# 3DPOV.net
KiCad netlist of a schematic drawn in EAGLE
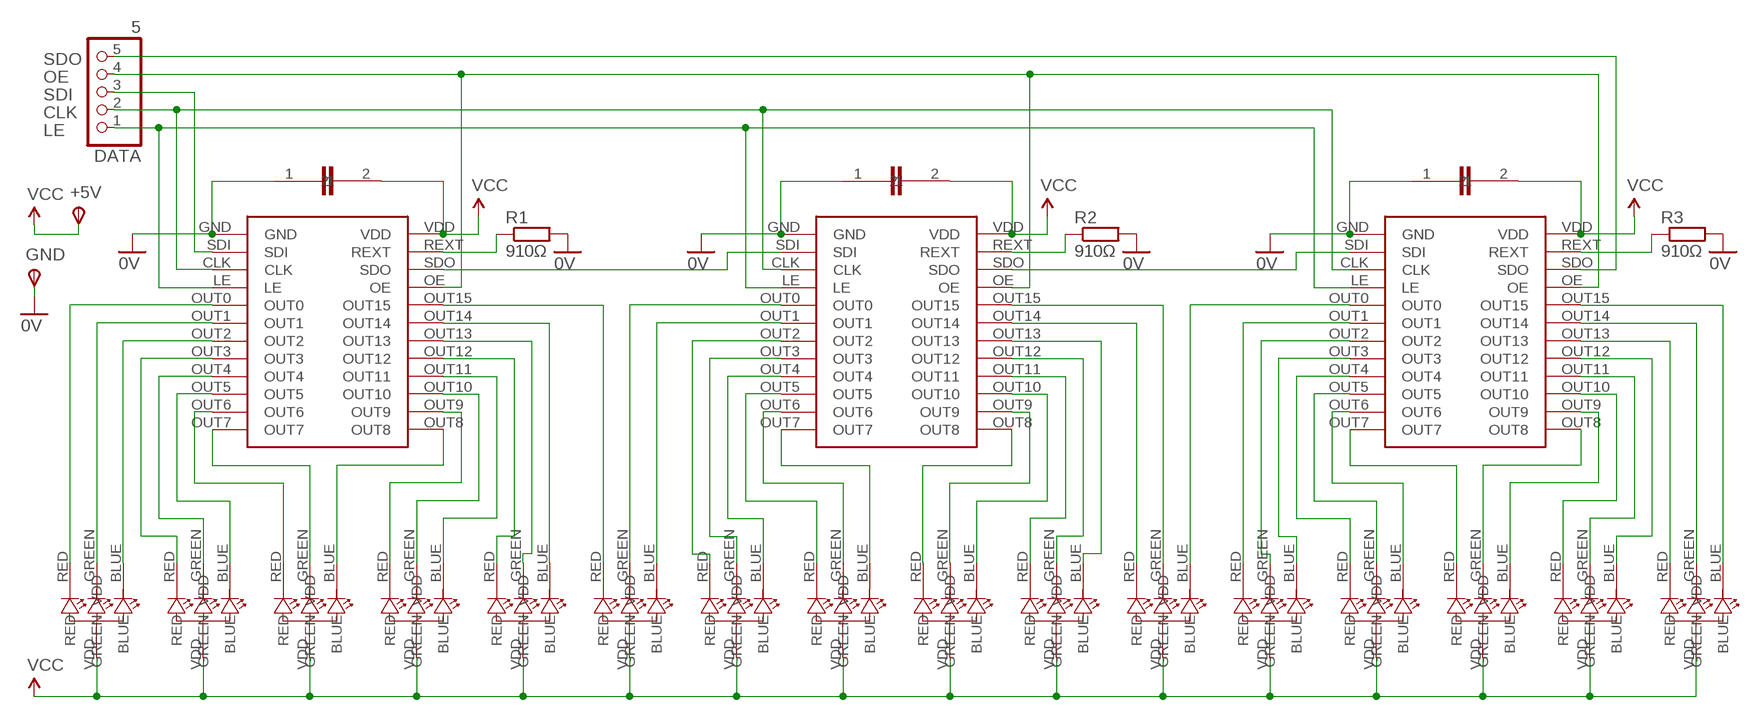
[diagram p0: schematic, sheet 1]

(export (version "E")
  (design (tool "Eeschema 10.0.6"))
  (components
    (comp (ref "+5V")
      (value "TPSPAD1-20")
      (footprint "eagle-import:P1-20")
      (libsource (lib "eagle-import") (part "TPSPAD1-20"))
    )
    (comp (ref "CAP1")
      (value "1µF")
      (footprint "eagle-import:CAP")
      (libsource (lib "eagle-import") (part "CAP"))
    )
    (comp (ref "CAP2")
      (value "1µF")
      (footprint "eagle-import:CAP")
      (libsource (lib "eagle-import") (part "CAP"))
    )
    (comp (ref "CAP3")
      (value "1µF")
      (footprint "eagle-import:CAP")
      (libsource (lib "eagle-import") (part "CAP"))
    )
    (comp (ref "DATA")
      (value "5")
      (footprint "eagle-import:1X05")
      (libsource (lib "eagle-import") (part "PINHD-1X5"))
    )
    (comp (ref "GND")
      (value "TPSPAD1-20")
      (footprint "eagle-import:P1-20")
      (libsource (lib "eagle-import") (part "TPSPAD1-20"))
    )
    (comp (ref "IC1")
      (value "TLC5927")
      (footprint "eagle-import:DBQ")
      (libsource (lib "eagle-import") (part "TLC5927"))
    )
    (comp (ref "IC2")
      (value "TLC5927")
      (footprint "eagle-import:DBQ")
      (libsource (lib "eagle-import") (part "TLC5927"))
    )
    (comp (ref "IC3")
      (value "TLC5927")
      (footprint "eagle-import:DBQ")
      (libsource (lib "eagle-import") (part "TLC5927"))
    )
    (comp (ref "R1")
      (value "910Ω")
      (footprint "eagle-import:0207_7")
      (libsource (lib "eagle-import") (part "R-EU_0207/7"))
    )
    (comp (ref "R2")
      (value "910Ω")
      (footprint "eagle-import:0207_7")
      (libsource (lib "eagle-import") (part "R-EU_0207/7"))
    )
    (comp (ref "R3")
      (value "910Ω")
      (footprint "eagle-import:0207_7")
      (libsource (lib "eagle-import") (part "R-EU_0207/7"))
    )
    (comp (ref "U$1")
      (value "SMDLED")
      (footprint "eagle-import:SMDLED")
      (libsource (lib "eagle-import") (part "SMDLED"))
    )
    (comp (ref "U$2")
      (value "SMDLED")
      (footprint "eagle-import:SMDLED")
      (libsource (lib "eagle-import") (part "SMDLED"))
    )
    (comp (ref "U$4")
      (value "SMDLED")
      (footprint "eagle-import:SMDLED")
      (libsource (lib "eagle-import") (part "SMDLED"))
    )
    (comp (ref "U$5")
      (value "SMDLED")
      (footprint "eagle-import:SMDLED")
      (libsource (lib "eagle-import") (part "SMDLED"))
    )
    (comp (ref "U$6")
      (value "SMDLED")
      (footprint "eagle-import:SMDLED")
      (libsource (lib "eagle-import") (part "SMDLED"))
    )
    (comp (ref "U$7")
      (value "SMDLED")
      (footprint "eagle-import:SMDLED")
      (libsource (lib "eagle-import") (part "SMDLED"))
    )
    (comp (ref "U$10")
      (value "SMDLED")
      (footprint "eagle-import:SMDLED")
      (libsource (lib "eagle-import") (part "SMDLED"))
    )
    (comp (ref "U$11")
      (value "SMDLED")
      (footprint "eagle-import:SMDLED")
      (libsource (lib "eagle-import") (part "SMDLED"))
    )
    (comp (ref "U$12")
      (value "SMDLED")
      (footprint "eagle-import:SMDLED")
      (libsource (lib "eagle-import") (part "SMDLED"))
    )
    (comp (ref "U$13")
      (value "SMDLED")
      (footprint "eagle-import:SMDLED")
      (libsource (lib "eagle-import") (part "SMDLED"))
    )
    (comp (ref "U$14")
      (value "SMDLED")
      (footprint "eagle-import:SMDLED")
      (libsource (lib "eagle-import") (part "SMDLED"))
    )
    (comp (ref "U$15")
      (value "SMDLED")
      (footprint "eagle-import:SMDLED")
      (libsource (lib "eagle-import") (part "SMDLED"))
    )
    (comp (ref "U$16")
      (value "SMDLED")
      (footprint "eagle-import:SMDLED")
      (libsource (lib "eagle-import") (part "SMDLED"))
    )
    (comp (ref "U$17")
      (value "SMDLED")
      (footprint "eagle-import:SMDLED")
      (libsource (lib "eagle-import") (part "SMDLED"))
    )
    (comp (ref "U$18")
      (value "SMDLED")
      (footprint "eagle-import:SMDLED")
      (libsource (lib "eagle-import") (part "SMDLED"))
    )
    (comp (ref "U$19")
      (value "SMDLED")
      (footprint "eagle-import:SMDLED")
      (libsource (lib "eagle-import") (part "SMDLED"))
    )
  )
  (nets
    (net (code "1") (name "/CLK") (class "Default")
      (node (ref "DATA") (pin "2") (pinfunction "2_2") (pintype "passive"))
      (node (ref "IC1") (pin "CLK") (pinfunction "CLK_CLK") (pintype "bidirectional"))
      (node (ref "IC2") (pin "CLK") (pinfunction "CLK_CLK") (pintype "bidirectional"))
      (node (ref "IC3") (pin "CLK") (pinfunction "CLK_CLK") (pintype "bidirectional"))
    )
    (net (code "2") (name "/LE") (class "Default")
      (node (ref "DATA") (pin "1") (pinfunction "1_1") (pintype "passive"))
      (node (ref "IC1") (pin "LE") (pinfunction "LE_LE") (pintype "bidirectional"))
      (node (ref "IC2") (pin "LE") (pinfunction "LE_LE") (pintype "bidirectional"))
      (node (ref "IC3") (pin "LE") (pinfunction "LE_LE") (pintype "bidirectional"))
    )
    (net (code "3") (name "/OE") (class "Default")
      (node (ref "DATA") (pin "4") (pinfunction "4_4") (pintype "passive"))
      (node (ref "IC1") (pin "OE") (pinfunction "OE_OE") (pintype "bidirectional"))
      (node (ref "IC2") (pin "OE") (pinfunction "OE_OE") (pintype "bidirectional"))
      (node (ref "IC3") (pin "OE") (pinfunction "OE_OE") (pintype "bidirectional"))
    )
    (net (code "4") (name "/SDI") (class "Default")
      (node (ref "DATA") (pin "3") (pinfunction "3_3") (pintype "passive"))
      (node (ref "IC1") (pin "SDI") (pinfunction "SDI_SDI") (pintype "bidirectional"))
    )
    (net (code "5") (name "/SDO") (class "Default")
      (node (ref "DATA") (pin "5") (pinfunction "5_5") (pintype "passive"))
      (node (ref "IC3") (pin "SDO") (pinfunction "SDO_SDO") (pintype "bidirectional"))
    )
    (net (code "6") (name "0V") (class "Default")
      (node (ref "CAP1") (pin "1") (pinfunction "1_1") (pintype "bidirectional"))
      (node (ref "CAP2") (pin "1") (pinfunction "1_1") (pintype "bidirectional"))
      (node (ref "CAP3") (pin "1") (pinfunction "1_1") (pintype "bidirectional"))
      (node (ref "GND") (pin "TP") (pinfunction "PP_TP") (pintype "input"))
      (node (ref "IC1") (pin "GND") (pinfunction "GND_GND") (pintype "bidirectional"))
      (node (ref "IC2") (pin "GND") (pinfunction "GND_GND") (pintype "bidirectional"))
      (node (ref "IC3") (pin "GND") (pinfunction "GND_GND") (pintype "bidirectional"))
      (node (ref "R1") (pin "2") (pinfunction "2_2") (pintype "passive"))
      (node (ref "R2") (pin "2") (pinfunction "2_2") (pintype "passive"))
      (node (ref "R3") (pin "2") (pinfunction "2_2") (pintype "passive"))
    )
    (net (code "7") (name "Net-(IC1-PadOUT0)") (class "Default")
      (node (ref "IC1") (pin "OUT0") (pinfunction "OUT0_OUT0") (pintype "bidirectional"))
      (node (ref "U$4") (pin "RED") (pinfunction "RED_RED") (pintype "bidirectional"))
    )
    (net (code "8") (name "Net-(IC1-PadOUT1)") (class "Default")
      (node (ref "IC1") (pin "OUT1") (pinfunction "OUT1_OUT1") (pintype "bidirectional"))
      (node (ref "U$4") (pin "GREEN") (pinfunction "GREEN_GREEN") (pintype "bidirectional"))
    )
    (net (code "9") (name "Net-(IC1-PadOUT2)") (class "Default")
      (node (ref "IC1") (pin "OUT2") (pinfunction "OUT2_OUT2") (pintype "bidirectional"))
      (node (ref "U$4") (pin "BLUE") (pinfunction "BLUE_BLUE") (pintype "bidirectional"))
    )
    (net (code "10") (name "Net-(IC1-PadOUT3)") (class "Default")
      (node (ref "IC1") (pin "OUT3") (pinfunction "OUT3_OUT3") (pintype "bidirectional"))
      (node (ref "U$5") (pin "RED") (pinfunction "RED_RED") (pintype "bidirectional"))
    )
    (net (code "11") (name "Net-(IC1-PadOUT4)") (class "Default")
      (node (ref "IC1") (pin "OUT4") (pinfunction "OUT4_OUT4") (pintype "bidirectional"))
      (node (ref "U$5") (pin "GREEN") (pinfunction "GREEN_GREEN") (pintype "bidirectional"))
    )
    (net (code "12") (name "Net-(IC1-PadOUT5)") (class "Default")
      (node (ref "IC1") (pin "OUT5") (pinfunction "OUT5_OUT5") (pintype "bidirectional"))
      (node (ref "U$5") (pin "BLUE") (pinfunction "BLUE_BLUE") (pintype "bidirectional"))
    )
    (net (code "13") (name "Net-(IC1-PadOUT6)") (class "Default")
      (node (ref "IC1") (pin "OUT6") (pinfunction "OUT6_OUT6") (pintype "bidirectional"))
      (node (ref "U$6") (pin "RED") (pinfunction "RED_RED") (pintype "bidirectional"))
    )
    (net (code "14") (name "Net-(IC1-PadOUT7)") (class "Default")
      (node (ref "IC1") (pin "OUT7") (pinfunction "OUT7_OUT7") (pintype "bidirectional"))
      (node (ref "U$6") (pin "GREEN") (pinfunction "GREEN_GREEN") (pintype "bidirectional"))
    )
    (net (code "15") (name "Net-(IC1-PadOUT8)") (class "Default")
      (node (ref "IC1") (pin "OUT8") (pinfunction "OUT8_OUT8") (pintype "bidirectional"))
      (node (ref "U$6") (pin "BLUE") (pinfunction "BLUE_BLUE") (pintype "bidirectional"))
    )
    (net (code "16") (name "Net-(IC1-PadOUT9)") (class "Default")
      (node (ref "IC1") (pin "OUT9") (pinfunction "OUT9_OUT9") (pintype "bidirectional"))
      (node (ref "U$7") (pin "RED") (pinfunction "RED_RED") (pintype "bidirectional"))
    )
    (net (code "17") (name "Net-(IC1-PadOUT10)") (class "Default")
      (node (ref "IC1") (pin "OUT10") (pinfunction "OUT10_OUT10") (pintype "bidirectional"))
      (node (ref "U$7") (pin "GREEN") (pinfunction "GREEN_GREEN") (pintype "bidirectional"))
    )
    (net (code "18") (name "Net-(IC1-PadOUT11)") (class "Default")
      (node (ref "IC1") (pin "OUT11") (pinfunction "OUT11_OUT11") (pintype "bidirectional"))
      (node (ref "U$7") (pin "BLUE") (pinfunction "BLUE_BLUE") (pintype "bidirectional"))
    )
    (net (code "19") (name "Net-(IC1-PadOUT12)") (class "Default")
      (node (ref "IC1") (pin "OUT12") (pinfunction "OUT12_OUT12") (pintype "bidirectional"))
      (node (ref "U$2") (pin "RED") (pinfunction "RED_RED") (pintype "bidirectional"))
    )
    (net (code "20") (name "Net-(IC1-PadOUT13)") (class "Default")
      (node (ref "IC1") (pin "OUT13") (pinfunction "OUT13_OUT13") (pintype "bidirectional"))
      (node (ref "U$2") (pin "GREEN") (pinfunction "GREEN_GREEN") (pintype "bidirectional"))
    )
    (net (code "21") (name "Net-(IC1-PadOUT14)") (class "Default")
      (node (ref "IC1") (pin "OUT14") (pinfunction "OUT14_OUT14") (pintype "bidirectional"))
      (node (ref "U$2") (pin "BLUE") (pinfunction "BLUE_BLUE") (pintype "bidirectional"))
    )
    (net (code "22") (name "Net-(IC1-PadOUT15)") (class "Default")
      (node (ref "IC1") (pin "OUT15") (pinfunction "OUT15_OUT15") (pintype "bidirectional"))
      (node (ref "U$1") (pin "RED") (pinfunction "RED_RED") (pintype "bidirectional"))
    )
    (net (code "23") (name "Net-(IC1-PadREXT)") (class "Default")
      (node (ref "IC1") (pin "REXT") (pinfunction "REXT_REXT") (pintype "bidirectional"))
      (node (ref "R1") (pin "1") (pinfunction "1_1") (pintype "passive"))
    )
    (net (code "24") (name "Net-(IC1-PadSDO)") (class "Default")
      (node (ref "IC1") (pin "SDO") (pinfunction "SDO_SDO") (pintype "bidirectional"))
      (node (ref "IC2") (pin "SDI") (pinfunction "SDI_SDI") (pintype "bidirectional"))
    )
    (net (code "25") (name "Net-(IC2-PadOUT0)") (class "Default")
      (node (ref "IC2") (pin "OUT0") (pinfunction "OUT0_OUT0") (pintype "bidirectional"))
      (node (ref "U$1") (pin "GREEN") (pinfunction "GREEN_GREEN") (pintype "bidirectional"))
    )
    (net (code "26") (name "Net-(IC2-PadOUT1)") (class "Default")
      (node (ref "IC2") (pin "OUT1") (pinfunction "OUT1_OUT1") (pintype "bidirectional"))
      (node (ref "U$1") (pin "BLUE") (pinfunction "BLUE_BLUE") (pintype "bidirectional"))
    )
    (net (code "27") (name "Net-(IC2-PadOUT2)") (class "Default")
      (node (ref "IC2") (pin "OUT2") (pinfunction "OUT2_OUT2") (pintype "bidirectional"))
      (node (ref "U$10") (pin "RED") (pinfunction "RED_RED") (pintype "bidirectional"))
    )
    (net (code "28") (name "Net-(IC2-PadOUT3)") (class "Default")
      (node (ref "IC2") (pin "OUT3") (pinfunction "OUT3_OUT3") (pintype "bidirectional"))
      (node (ref "U$10") (pin "GREEN") (pinfunction "GREEN_GREEN") (pintype "bidirectional"))
    )
    (net (code "29") (name "Net-(IC2-PadOUT4)") (class "Default")
      (node (ref "IC2") (pin "OUT4") (pinfunction "OUT4_OUT4") (pintype "bidirectional"))
      (node (ref "U$10") (pin "BLUE") (pinfunction "BLUE_BLUE") (pintype "bidirectional"))
    )
    (net (code "30") (name "Net-(IC2-PadOUT5)") (class "Default")
      (node (ref "IC2") (pin "OUT5") (pinfunction "OUT5_OUT5") (pintype "bidirectional"))
      (node (ref "U$11") (pin "RED") (pinfunction "RED_RED") (pintype "bidirectional"))
    )
    (net (code "31") (name "Net-(IC2-PadOUT6)") (class "Default")
      (node (ref "IC2") (pin "OUT6") (pinfunction "OUT6_OUT6") (pintype "bidirectional"))
      (node (ref "U$11") (pin "GREEN") (pinfunction "GREEN_GREEN") (pintype "bidirectional"))
    )
    (net (code "32") (name "Net-(IC2-PadOUT7)") (class "Default")
      (node (ref "IC2") (pin "OUT7") (pinfunction "OUT7_OUT7") (pintype "bidirectional"))
      (node (ref "U$11") (pin "BLUE") (pinfunction "BLUE_BLUE") (pintype "bidirectional"))
    )
    (net (code "33") (name "Net-(IC2-PadOUT8)") (class "Default")
      (node (ref "IC2") (pin "OUT8") (pinfunction "OUT8_OUT8") (pintype "bidirectional"))
      (node (ref "U$12") (pin "RED") (pinfunction "RED_RED") (pintype "bidirectional"))
    )
    (net (code "34") (name "Net-(IC2-PadOUT9)") (class "Default")
      (node (ref "IC2") (pin "OUT9") (pinfunction "OUT9_OUT9") (pintype "bidirectional"))
      (node (ref "U$12") (pin "GREEN") (pinfunction "GREEN_GREEN") (pintype "bidirectional"))
    )
    (net (code "35") (name "Net-(IC2-PadOUT10)") (class "Default")
      (node (ref "IC2") (pin "OUT10") (pinfunction "OUT10_OUT10") (pintype "bidirectional"))
      (node (ref "U$12") (pin "BLUE") (pinfunction "BLUE_BLUE") (pintype "bidirectional"))
    )
    (net (code "36") (name "Net-(IC2-PadOUT11)") (class "Default")
      (node (ref "IC2") (pin "OUT11") (pinfunction "OUT11_OUT11") (pintype "bidirectional"))
      (node (ref "U$13") (pin "RED") (pinfunction "RED_RED") (pintype "bidirectional"))
    )
    (net (code "37") (name "Net-(IC2-PadOUT12)") (class "Default")
      (node (ref "IC2") (pin "OUT12") (pinfunction "OUT12_OUT12") (pintype "bidirectional"))
      (node (ref "U$13") (pin "GREEN") (pinfunction "GREEN_GREEN") (pintype "bidirectional"))
    )
    (net (code "38") (name "Net-(IC2-PadOUT13)") (class "Default")
      (node (ref "IC2") (pin "OUT13") (pinfunction "OUT13_OUT13") (pintype "bidirectional"))
      (node (ref "U$13") (pin "BLUE") (pinfunction "BLUE_BLUE") (pintype "bidirectional"))
    )
    (net (code "39") (name "Net-(IC2-PadOUT14)") (class "Default")
      (node (ref "IC2") (pin "OUT14") (pinfunction "OUT14_OUT14") (pintype "bidirectional"))
      (node (ref "U$14") (pin "RED") (pinfunction "RED_RED") (pintype "bidirectional"))
    )
    (net (code "40") (name "Net-(IC2-PadOUT15)") (class "Default")
      (node (ref "IC2") (pin "OUT15") (pinfunction "OUT15_OUT15") (pintype "bidirectional"))
      (node (ref "U$14") (pin "GREEN") (pinfunction "GREEN_GREEN") (pintype "bidirectional"))
    )
    (net (code "41") (name "Net-(IC2-PadREXT)") (class "Default")
      (node (ref "IC2") (pin "REXT") (pinfunction "REXT_REXT") (pintype "bidirectional"))
      (node (ref "R2") (pin "1") (pinfunction "1_1") (pintype "passive"))
    )
    (net (code "42") (name "Net-(IC2-PadSDO)") (class "Default")
      (node (ref "IC2") (pin "SDO") (pinfunction "SDO_SDO") (pintype "bidirectional"))
      (node (ref "IC3") (pin "SDI") (pinfunction "SDI_SDI") (pintype "bidirectional"))
    )
    (net (code "43") (name "Net-(IC3-PadOUT0)") (class "Default")
      (node (ref "IC3") (pin "OUT0") (pinfunction "OUT0_OUT0") (pintype "bidirectional"))
      (node (ref "U$14") (pin "BLUE") (pinfunction "BLUE_BLUE") (pintype "bidirectional"))
    )
    (net (code "44") (name "Net-(IC3-PadOUT1)") (class "Default")
      (node (ref "IC3") (pin "OUT1") (pinfunction "OUT1_OUT1") (pintype "bidirectional"))
      (node (ref "U$15") (pin "RED") (pinfunction "RED_RED") (pintype "bidirectional"))
    )
    (net (code "45") (name "Net-(IC3-PadOUT2)") (class "Default")
      (node (ref "IC3") (pin "OUT2") (pinfunction "OUT2_OUT2") (pintype "bidirectional"))
      (node (ref "U$15") (pin "GREEN") (pinfunction "GREEN_GREEN") (pintype "bidirectional"))
    )
    (net (code "46") (name "Net-(IC3-PadOUT3)") (class "Default")
      (node (ref "IC3") (pin "OUT3") (pinfunction "OUT3_OUT3") (pintype "bidirectional"))
      (node (ref "U$15") (pin "BLUE") (pinfunction "BLUE_BLUE") (pintype "bidirectional"))
    )
    (net (code "47") (name "Net-(IC3-PadOUT4)") (class "Default")
      (node (ref "IC3") (pin "OUT4") (pinfunction "OUT4_OUT4") (pintype "bidirectional"))
      (node (ref "U$16") (pin "RED") (pinfunction "RED_RED") (pintype "bidirectional"))
    )
    (net (code "48") (name "Net-(IC3-PadOUT5)") (class "Default")
      (node (ref "IC3") (pin "OUT5") (pinfunction "OUT5_OUT5") (pintype "bidirectional"))
      (node (ref "U$16") (pin "GREEN") (pinfunction "GREEN_GREEN") (pintype "bidirectional"))
    )
    (net (code "49") (name "Net-(IC3-PadOUT6)") (class "Default")
      (node (ref "IC3") (pin "OUT6") (pinfunction "OUT6_OUT6") (pintype "bidirectional"))
      (node (ref "U$16") (pin "BLUE") (pinfunction "BLUE_BLUE") (pintype "bidirectional"))
    )
    (net (code "50") (name "Net-(IC3-PadOUT7)") (class "Default")
      (node (ref "IC3") (pin "OUT7") (pinfunction "OUT7_OUT7") (pintype "bidirectional"))
      (node (ref "U$17") (pin "RED") (pinfunction "RED_RED") (pintype "bidirectional"))
    )
    (net (code "51") (name "Net-(IC3-PadOUT8)") (class "Default")
      (node (ref "IC3") (pin "OUT8") (pinfunction "OUT8_OUT8") (pintype "bidirectional"))
      (node (ref "U$17") (pin "GREEN") (pinfunction "GREEN_GREEN") (pintype "bidirectional"))
    )
    (net (code "52") (name "Net-(IC3-PadOUT9)") (class "Default")
      (node (ref "IC3") (pin "OUT9") (pinfunction "OUT9_OUT9") (pintype "bidirectional"))
      (node (ref "U$17") (pin "BLUE") (pinfunction "BLUE_BLUE") (pintype "bidirectional"))
    )
    (net (code "53") (name "Net-(IC3-PadOUT10)") (class "Default")
      (node (ref "IC3") (pin "OUT10") (pinfunction "OUT10_OUT10") (pintype "bidirectional"))
      (node (ref "U$18") (pin "RED") (pinfunction "RED_RED") (pintype "bidirectional"))
    )
    (net (code "54") (name "Net-(IC3-PadOUT11)") (class "Default")
      (node (ref "IC3") (pin "OUT11") (pinfunction "OUT11_OUT11") (pintype "bidirectional"))
      (node (ref "U$18") (pin "GREEN") (pinfunction "GREEN_GREEN") (pintype "bidirectional"))
    )
    (net (code "55") (name "Net-(IC3-PadOUT12)") (class "Default")
      (node (ref "IC3") (pin "OUT12") (pinfunction "OUT12_OUT12") (pintype "bidirectional"))
      (node (ref "U$18") (pin "BLUE") (pinfunction "BLUE_BLUE") (pintype "bidirectional"))
    )
    (net (code "56") (name "Net-(IC3-PadOUT13)") (class "Default")
      (node (ref "IC3") (pin "OUT13") (pinfunction "OUT13_OUT13") (pintype "bidirectional"))
      (node (ref "U$19") (pin "RED") (pinfunction "RED_RED") (pintype "bidirectional"))
    )
    (net (code "57") (name "Net-(IC3-PadOUT14)") (class "Default")
      (node (ref "IC3") (pin "OUT14") (pinfunction "OUT14_OUT14") (pintype "bidirectional"))
      (node (ref "U$19") (pin "GREEN") (pinfunction "GREEN_GREEN") (pintype "bidirectional"))
    )
    (net (code "58") (name "Net-(IC3-PadOUT15)") (class "Default")
      (node (ref "IC3") (pin "OUT15") (pinfunction "OUT15_OUT15") (pintype "bidirectional"))
      (node (ref "U$19") (pin "BLUE") (pinfunction "BLUE_BLUE") (pintype "bidirectional"))
    )
    (net (code "59") (name "Net-(IC3-PadREXT)") (class "Default")
      (node (ref "IC3") (pin "REXT") (pinfunction "REXT_REXT") (pintype "bidirectional"))
      (node (ref "R3") (pin "1") (pinfunction "1_1") (pintype "passive"))
    )
    (net (code "60") (name "VCC") (class "Default")
      (node (ref "+5V") (pin "TP") (pinfunction "PP_TP") (pintype "input"))
      (node (ref "CAP1") (pin "2") (pinfunction "2_2") (pintype "bidirectional"))
      (node (ref "CAP2") (pin "2") (pinfunction "2_2") (pintype "bidirectional"))
      (node (ref "CAP3") (pin "2") (pinfunction "2_2") (pintype "bidirectional"))
      (node (ref "IC1") (pin "VDD") (pinfunction "VDD_VDD") (pintype "bidirectional"))
      (node (ref "IC2") (pin "VDD") (pinfunction "VDD_VDD") (pintype "bidirectional"))
      (node (ref "IC3") (pin "VDD") (pinfunction "VDD_VDD") (pintype "bidirectional"))
      (node (ref "U$1") (pin "VDD") (pinfunction "VDD_VDD") (pintype "bidirectional"))
      (node (ref "U$10") (pin "VDD") (pinfunction "VDD_VDD") (pintype "bidirectional"))
      (node (ref "U$11") (pin "VDD") (pinfunction "VDD_VDD") (pintype "bidirectional"))
      (node (ref "U$12") (pin "VDD") (pinfunction "VDD_VDD") (pintype "bidirectional"))
      (node (ref "U$13") (pin "VDD") (pinfunction "VDD_VDD") (pintype "bidirectional"))
      (node (ref "U$14") (pin "VDD") (pinfunction "VDD_VDD") (pintype "bidirectional"))
      (node (ref "U$15") (pin "VDD") (pinfunction "VDD_VDD") (pintype "bidirectional"))
      (node (ref "U$16") (pin "VDD") (pinfunction "VDD_VDD") (pintype "bidirectional"))
      (node (ref "U$17") (pin "VDD") (pinfunction "VDD_VDD") (pintype "bidirectional"))
      (node (ref "U$18") (pin "VDD") (pinfunction "VDD_VDD") (pintype "bidirectional"))
      (node (ref "U$19") (pin "VDD") (pinfunction "VDD_VDD") (pintype "bidirectional"))
      (node (ref "U$2") (pin "VDD") (pinfunction "VDD_VDD") (pintype "bidirectional"))
      (node (ref "U$4") (pin "VDD") (pinfunction "VDD_VDD") (pintype "bidirectional"))
      (node (ref "U$5") (pin "VDD") (pinfunction "VDD_VDD") (pintype "bidirectional"))
      (node (ref "U$6") (pin "VDD") (pinfunction "VDD_VDD") (pintype "bidirectional"))
      (node (ref "U$7") (pin "VDD") (pinfunction "VDD_VDD") (pintype "bidirectional"))
    )
  )
)
